# guhPLC_6LowPANModule.net
KiCad netlist of a schematic drawn in EAGLE
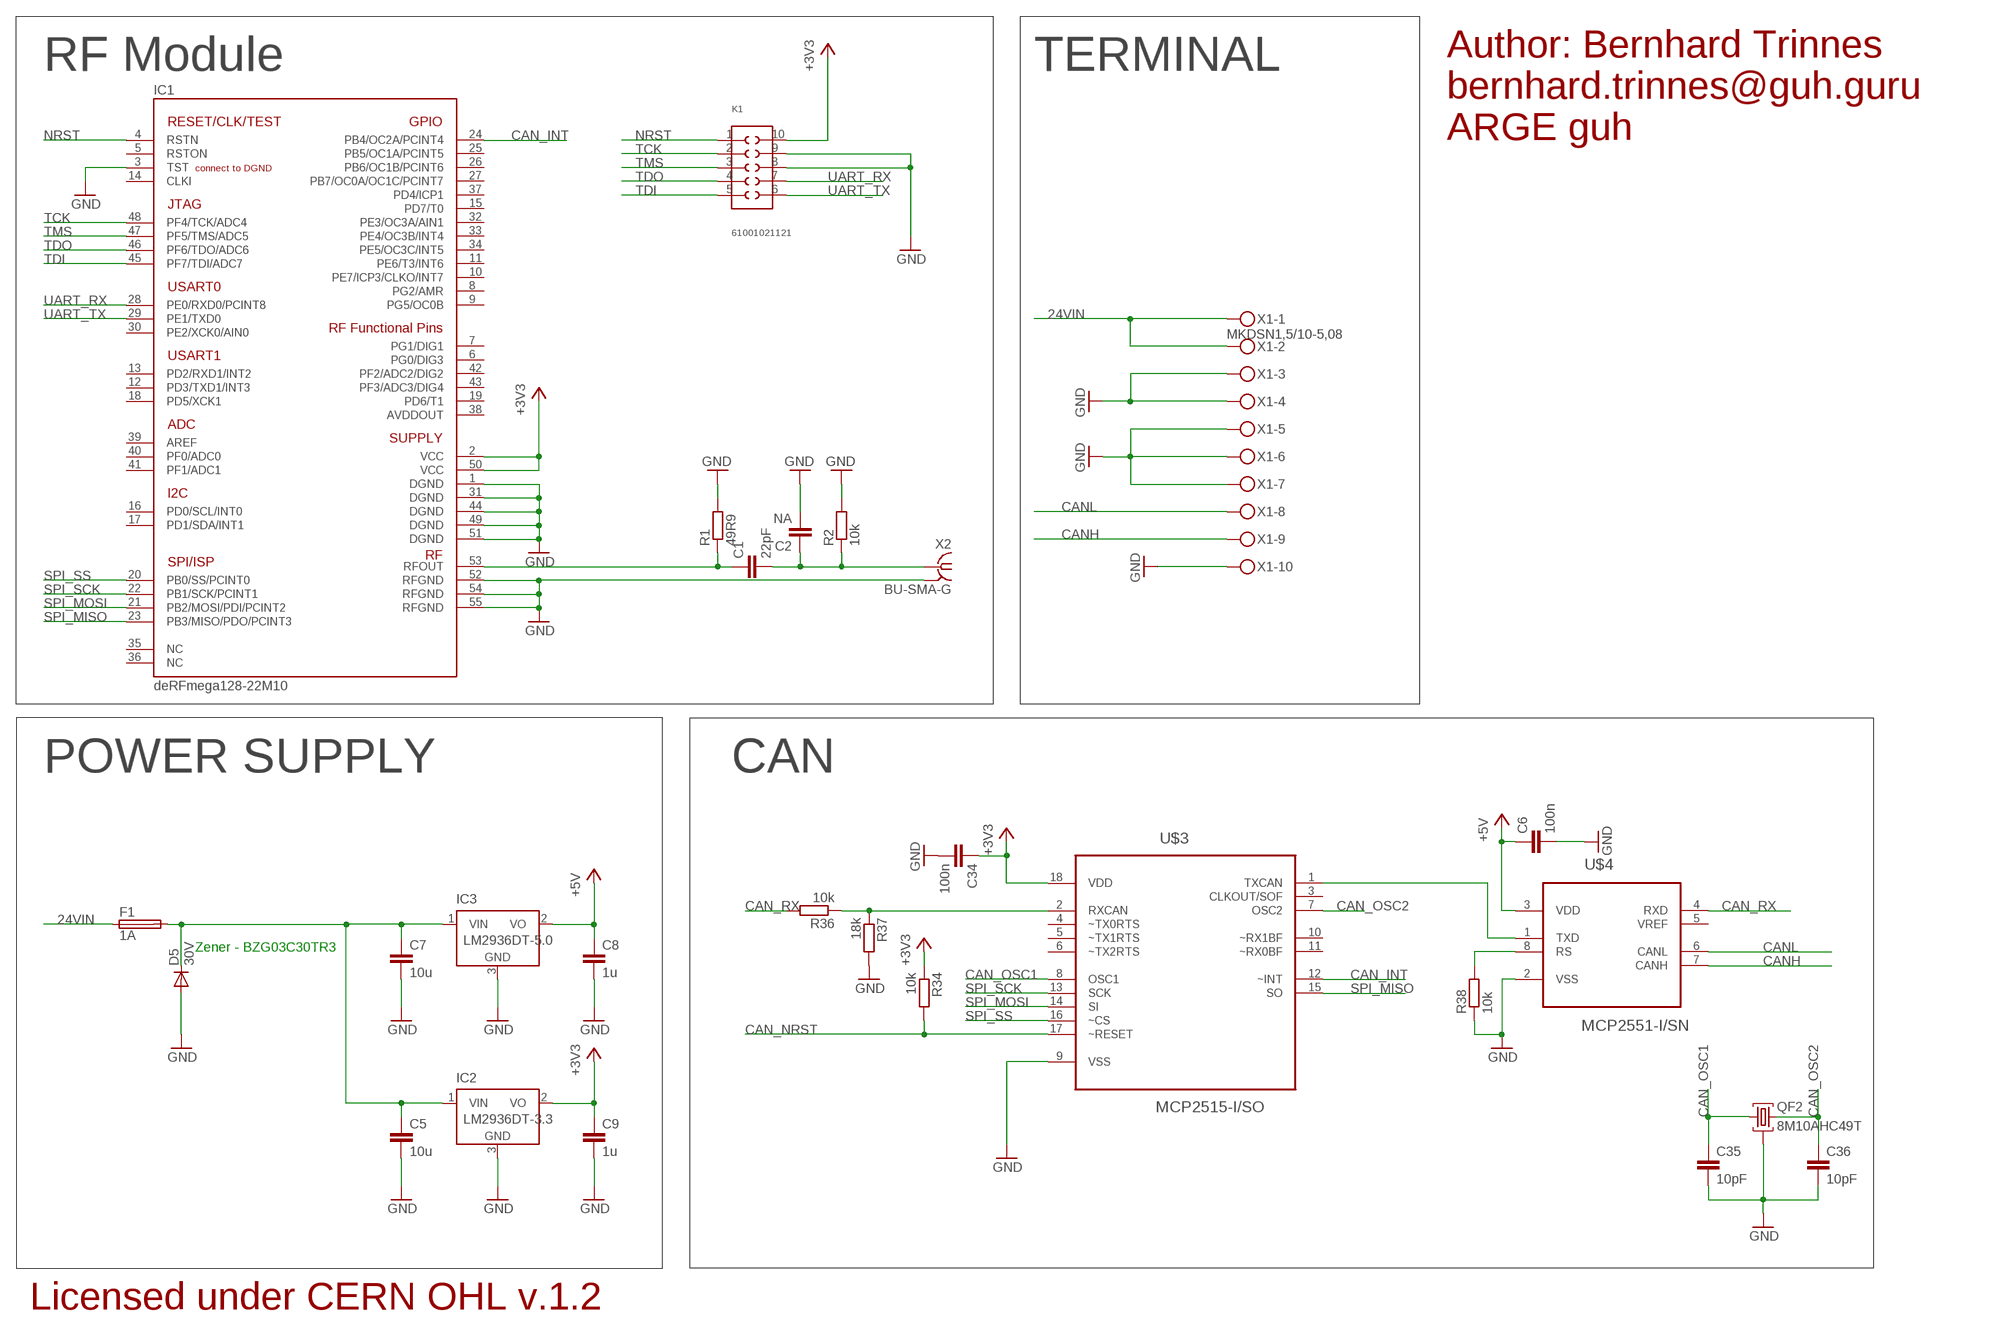
[diagram p0: schematic, sheet 1]

(export (version "E")
  (design (tool "Eeschema 10.0.6"))
  (components
    (comp (ref "C1")
      (value "22pF")
      (footprint "eagle-import:C0402")
      (libsource (lib "eagle-import") (part "C-EUC0402"))
    )
    (comp (ref "C2")
      (value "NA")
      (footprint "eagle-import:C0402")
      (libsource (lib "eagle-import") (part "C-EUC0402"))
    )
    (comp (ref "C5")
      (value "10u")
      (footprint "eagle-import:C1206")
      (libsource (lib "eagle-import") (part "C-EUC1206"))
    )
    (comp (ref "C6")
      (value "100n")
      (footprint "eagle-import:C0603")
      (libsource (lib "eagle-import") (part "C-EUC0603"))
    )
    (comp (ref "C7")
      (value "10u")
      (footprint "eagle-import:C1206")
      (libsource (lib "eagle-import") (part "C-EUC1206"))
    )
    (comp (ref "C8")
      (value "1u")
      (footprint "eagle-import:C0603")
      (libsource (lib "eagle-import") (part "C-EUC0603"))
    )
    (comp (ref "C9")
      (value "1u")
      (footprint "eagle-import:C0603")
      (libsource (lib "eagle-import") (part "C-EUC0603"))
    )
    (comp (ref "C34")
      (value "100n")
      (footprint "eagle-import:C0603")
      (libsource (lib "eagle-import") (part "C-EUC0603"))
    )
    (comp (ref "C35")
      (value "10pF")
      (footprint "eagle-import:C0603")
      (libsource (lib "eagle-import") (part "C-EUC0603"))
    )
    (comp (ref "C36")
      (value "10pF")
      (footprint "eagle-import:C0603")
      (libsource (lib "eagle-import") (part "C-EUC0603"))
    )
    (comp (ref "D5")
      (value "30V")
      (footprint "eagle-import:DO214AC")
      (libsource (lib "eagle-import") (part "DIODE-DO214AC"))
    )
    (comp (ref "F1")
      (value "1A")
      (footprint "eagle-import:LITTLEFUSE")
      (libsource (lib "eagle-import") (part "LITTLEFUSE"))
    )
    (comp (ref "IC1")
      (value "DERFMEGA128-22M10")
      (footprint "eagle-import:A-M10")
      (libsource (lib "eagle-import") (part "DERFMEGA128-22M10"))
    )
    (comp (ref "IC2")
      (value "LM2936DT-3.3")
      (footprint "eagle-import:TO252")
      (fields (field (name "MPN") "LM2936DT-3.3."))
      (libsource (lib "eagle-import") (part "LM2936?DT-3.3"))
    )
    (comp (ref "IC3")
      (value "LM2936DT-5.0")
      (footprint "eagle-import:TO252")
      (fields (field (name "MF") "NATIONAL SEMICONDUCTOR") (field (name "MPN") "LM2936DT-5.0/NOPB"))
      (libsource (lib "eagle-import") (part "LM2936?DT-5.0"))
    )
    (comp (ref "K1")
      (value "61001021121")
      (footprint "eagle-import:61001021121")
      (libsource (lib "eagle-import") (part "61001021121"))
    )
    (comp (ref "QF2")
      (value "8M10AHC49T")
      (footprint "eagle-import:HC49U")
      (fields (field (name "OC_FARNELL") "unknown") (field (name "OC_NEWARK") "unknown"))
      (libsource (lib "eagle-import") (part "8M10AHC49T"))
    )
    (comp (ref "R1")
      (value "49R9")
      (footprint "eagle-import:R0402")
      (libsource (lib "eagle-import") (part "R-EU_R0402"))
    )
    (comp (ref "R2")
      (value "10k")
      (footprint "eagle-import:R0402")
      (libsource (lib "eagle-import") (part "R-EU_R0402"))
    )
    (comp (ref "R34")
      (value "10k")
      (footprint "eagle-import:R0603")
      (libsource (lib "eagle-import") (part "R-EU_R0603"))
    )
    (comp (ref "R36")
      (value "10k")
      (footprint "eagle-import:R0603")
      (libsource (lib "eagle-import") (part "R-EU_R0603"))
    )
    (comp (ref "R37")
      (value "18k")
      (footprint "eagle-import:R0603")
      (libsource (lib "eagle-import") (part "R-EU_R0603"))
    )
    (comp (ref "R38")
      (value "10k")
      (footprint "eagle-import:R0603")
      (libsource (lib "eagle-import") (part "R-EU_R0603"))
    )
    (comp (ref "U$3")
      (value "MCP2515-I/SO")
      (footprint "eagle-import:SOIC127P1034X264-18N")
      (libsource (lib "eagle-import") (part "MCP2515-I/SO"))
    )
    (comp (ref "U$4")
      (value "MCP2551-I/SN")
      (footprint "eagle-import:SOIC127P600X175-8N")
      (libsource (lib "eagle-import") (part "MCP2551-I/SN"))
    )
    (comp (ref "X1")
      (value "MKDSN1,5/10-5,08")
      (footprint "eagle-import:MKDSN1,5_10-5,08")
      (fields (field (name "MPN") "SMKDSN1,5/10-5,08"))
      (libsource (lib "eagle-import") (part "MKDSN1,5/10-5,08"))
    )
    (comp (ref "X2")
      (value "BU-SMA-G")
      (footprint "eagle-import:BU-SMA-G")
      (libsource (lib "eagle-import") (part "BU-SMA-G"))
    )
  )
  (nets
    (net (code "1") (name "+3V3") (class "Default")
      (node (ref "C34") (pin "1") (pinfunction "1_1") (pintype "passive"))
      (node (ref "C9") (pin "1") (pinfunction "1_1") (pintype "passive"))
      (node (ref "IC1") (pin "2") (pinfunction "VCC_2") (pintype "power_in"))
      (node (ref "IC1") (pin "50") (pinfunction "VCC_50") (pintype "power_in"))
      (node (ref "IC2") (pin "2") (pinfunction "VO_2") (pintype "passive"))
      (node (ref "K1") (pin "10") (pinfunction "10_10") (pintype "passive"))
      (node (ref "R34") (pin "1") (pinfunction "1_1") (pintype "passive"))
      (node (ref "U$3") (pin "18") (pinfunction "VDD_18") (pintype "power_in"))
    )
    (net (code "2") (name "+5V") (class "Default")
      (node (ref "C6") (pin "1") (pinfunction "1_1") (pintype "passive"))
      (node (ref "C8") (pin "1") (pinfunction "1_1") (pintype "passive"))
      (node (ref "IC3") (pin "2") (pinfunction "VO_2") (pintype "passive"))
      (node (ref "U$4") (pin "3") (pinfunction "VDD_3") (pintype "power_in"))
    )
    (net (code "3") (name "/24VIN") (class "Default")
      (node (ref "F1") (pin "1") (pinfunction "1_1") (pintype "passive"))
      (node (ref "X1") (pin "1") (pinfunction "KL_1") (pintype "passive"))
      (node (ref "X1") (pin "2") (pinfunction "KL_2") (pintype "passive"))
    )
    (net (code "4") (name "/CANH") (class "Default")
      (node (ref "U$4") (pin "7") (pinfunction "CANH_7") (pintype "bidirectional"))
      (node (ref "X1") (pin "9") (pinfunction "KL_9") (pintype "passive"))
    )
    (net (code "5") (name "/CANL") (class "Default")
      (node (ref "U$4") (pin "6") (pinfunction "CANL_6") (pintype "bidirectional"))
      (node (ref "X1") (pin "8") (pinfunction "KL_8") (pintype "passive"))
    )
    (net (code "6") (name "/CAN_INT") (class "Default")
      (node (ref "IC1") (pin "24") (pinfunction "PB4/OC2A/PCINT4_24") (pintype "bidirectional"))
      (node (ref "U$3") (pin "12") (pinfunction "~{INT}_12") (pintype "output"))
    )
    (net (code "7") (name "/CAN_NRST") (class "Default")
      (node (ref "R34") (pin "2") (pinfunction "2_2") (pintype "passive"))
      (node (ref "U$3") (pin "17") (pinfunction "~{RESET}_17") (pintype "input"))
    )
    (net (code "8") (name "/CAN_OSC1") (class "Default")
      (node (ref "C35") (pin "1") (pinfunction "1_1") (pintype "passive"))
      (node (ref "QF2") (pin "1") (pinfunction "1_1") (pintype "passive"))
      (node (ref "U$3") (pin "8") (pinfunction "OSC1_8") (pintype "input"))
    )
    (net (code "9") (name "/CAN_OSC2") (class "Default")
      (node (ref "C36") (pin "1") (pinfunction "1_1") (pintype "passive"))
      (node (ref "QF2") (pin "3") (pinfunction "3_3") (pintype "passive"))
      (node (ref "U$3") (pin "7") (pinfunction "OSC2_7") (pintype "output"))
    )
    (net (code "10") (name "/CAN_RX") (class "Default")
      (node (ref "R36") (pin "2") (pinfunction "2_2") (pintype "passive"))
      (node (ref "U$4") (pin "4") (pinfunction "RXD_4") (pintype "output"))
    )
    (net (code "11") (name "/NRST") (class "Default")
      (node (ref "IC1") (pin "4") (pinfunction "RSTN_4") (pintype "input"))
      (node (ref "K1") (pin "1") (pinfunction "1_1") (pintype "passive"))
    )
    (net (code "12") (name "/SPI_MISO") (class "Default")
      (node (ref "IC1") (pin "23") (pinfunction "PB3/MISO/PDO/PCINT3_23") (pintype "bidirectional"))
      (node (ref "U$3") (pin "15") (pinfunction "SO_15") (pintype "output"))
    )
    (net (code "13") (name "/SPI_MOSI") (class "Default")
      (node (ref "IC1") (pin "21") (pinfunction "PB2/MOSI/PDI/PCINT2_21") (pintype "bidirectional"))
      (node (ref "U$3") (pin "14") (pinfunction "SI_14") (pintype "input"))
    )
    (net (code "14") (name "/SPI_SCK") (class "Default")
      (node (ref "IC1") (pin "22") (pinfunction "PB1/SCK/PCINT1_22") (pintype "bidirectional"))
      (node (ref "U$3") (pin "13") (pinfunction "SCK_13") (pintype "input"))
    )
    (net (code "15") (name "/SPI_SS") (class "Default")
      (node (ref "IC1") (pin "20") (pinfunction "PB0/SS/PCINT0_20") (pintype "bidirectional"))
      (node (ref "U$3") (pin "16") (pinfunction "~{CS}_16") (pintype "input"))
    )
    (net (code "16") (name "/TCK") (class "Default")
      (node (ref "IC1") (pin "48") (pinfunction "PF4/TCK/ADC4_48") (pintype "bidirectional"))
      (node (ref "K1") (pin "2") (pinfunction "2_2") (pintype "passive"))
    )
    (net (code "17") (name "/TDI") (class "Default")
      (node (ref "IC1") (pin "45") (pinfunction "PF7/TDI/ADC7_45") (pintype "bidirectional"))
      (node (ref "K1") (pin "5") (pinfunction "5_5") (pintype "passive"))
    )
    (net (code "18") (name "/TDO") (class "Default")
      (node (ref "IC1") (pin "46") (pinfunction "PF6/TDO/ADC6_46") (pintype "bidirectional"))
      (node (ref "K1") (pin "4") (pinfunction "4_4") (pintype "passive"))
    )
    (net (code "19") (name "/TMS") (class "Default")
      (node (ref "IC1") (pin "47") (pinfunction "PF5/TMS/ADC5_47") (pintype "bidirectional"))
      (node (ref "K1") (pin "3") (pinfunction "3_3") (pintype "passive"))
    )
    (net (code "20") (name "/UART_RX") (class "Default")
      (node (ref "IC1") (pin "28") (pinfunction "PE0/RXD0/PCINT8_28") (pintype "bidirectional"))
      (node (ref "K1") (pin "7") (pinfunction "7_7") (pintype "passive"))
    )
    (net (code "21") (name "/UART_TX") (class "Default")
      (node (ref "IC1") (pin "29") (pinfunction "PE1/TXD0_29") (pintype "bidirectional"))
      (node (ref "K1") (pin "6") (pinfunction "6_6") (pintype "passive"))
    )
    (net (code "22") (name "GND") (class "Default")
      (node (ref "C2") (pin "2") (pinfunction "2_2") (pintype "passive"))
      (node (ref "C34") (pin "2") (pinfunction "2_2") (pintype "passive"))
      (node (ref "C35") (pin "2") (pinfunction "2_2") (pintype "passive"))
      (node (ref "C36") (pin "2") (pinfunction "2_2") (pintype "passive"))
      (node (ref "C5") (pin "2") (pinfunction "2_2") (pintype "passive"))
      (node (ref "C6") (pin "2") (pinfunction "2_2") (pintype "passive"))
      (node (ref "C7") (pin "2") (pinfunction "2_2") (pintype "passive"))
      (node (ref "C8") (pin "2") (pinfunction "2_2") (pintype "passive"))
      (node (ref "C9") (pin "2") (pinfunction "2_2") (pintype "passive"))
      (node (ref "D5") (pin "A") (pinfunction "A_A") (pintype "passive"))
      (node (ref "IC1") (pin "1") (pinfunction "DGND_1") (pintype "power_in"))
      (node (ref "IC1") (pin "3") (pinfunction "TST_3") (pintype "input"))
      (node (ref "IC1") (pin "31") (pinfunction "DGND_31") (pintype "power_in"))
      (node (ref "IC1") (pin "44") (pinfunction "DGND_44") (pintype "power_in"))
      (node (ref "IC1") (pin "49") (pinfunction "DGND_49") (pintype "power_in"))
      (node (ref "IC1") (pin "51") (pinfunction "DGND_51") (pintype "power_in"))
      (node (ref "IC1") (pin "52") (pinfunction "RFGND_52") (pintype "power_in"))
      (node (ref "IC1") (pin "54") (pinfunction "RFGND_54") (pintype "power_in"))
      (node (ref "IC1") (pin "55") (pinfunction "RFGND_55") (pintype "power_in"))
      (node (ref "IC2") (pin "3") (pinfunction "GND_3") (pintype "passive"))
      (node (ref "IC3") (pin "3") (pinfunction "GND_3") (pintype "passive"))
      (node (ref "K1") (pin "8") (pinfunction "8_8") (pintype "passive"))
      (node (ref "K1") (pin "9") (pinfunction "9_9") (pintype "passive"))
      (node (ref "QF2") (pin "2") (pinfunction "2_2") (pintype "passive"))
      (node (ref "R1") (pin "2") (pinfunction "2_2") (pintype "passive"))
      (node (ref "R2") (pin "2") (pinfunction "2_2") (pintype "passive"))
      (node (ref "R37") (pin "2") (pinfunction "2_2") (pintype "passive"))
      (node (ref "R38") (pin "1") (pinfunction "1_1") (pintype "passive"))
      (node (ref "U$3") (pin "9") (pinfunction "VSS_9") (pintype "power_in"))
      (node (ref "U$4") (pin "2") (pinfunction "VSS_2") (pintype "passive"))
      (node (ref "X1") (pin "10") (pinfunction "KL_10") (pintype "passive"))
      (node (ref "X1") (pin "3") (pinfunction "KL_3") (pintype "passive"))
      (node (ref "X1") (pin "4") (pinfunction "KL_4") (pintype "passive"))
      (node (ref "X1") (pin "5") (pinfunction "KL_5") (pintype "passive"))
      (node (ref "X1") (pin "6") (pinfunction "KL_6") (pintype "passive"))
      (node (ref "X1") (pin "7") (pinfunction "KL_7") (pintype "passive"))
      (node (ref "X2") (pin "2") (pinfunction "GND_2") (pintype "power_in"))
    )
    (net (code "23") (name "Net-(C1-Pad2)") (class "Default")
      (node (ref "C1") (pin "2") (pinfunction "2_2") (pintype "passive"))
      (node (ref "C2") (pin "1") (pinfunction "1_1") (pintype "passive"))
      (node (ref "R2") (pin "1") (pinfunction "1_1") (pintype "passive"))
      (node (ref "X2") (pin "1") (pinfunction "1_1") (pintype "passive"))
    )
    (net (code "24") (name "Net-(IC1-RFOUT)") (class "Default")
      (node (ref "C1") (pin "1") (pinfunction "1_1") (pintype "passive"))
      (node (ref "IC1") (pin "53") (pinfunction "RFOUT_53") (pintype "power_in"))
      (node (ref "R1") (pin "1") (pinfunction "1_1") (pintype "passive"))
    )
    (net (code "25") (name "Net-(IC2-VIN)") (class "Default")
      (node (ref "C5") (pin "1") (pinfunction "1_1") (pintype "passive"))
      (node (ref "C7") (pin "1") (pinfunction "1_1") (pintype "passive"))
      (node (ref "D5") (pin "C") (pinfunction "C_C") (pintype "passive"))
      (node (ref "F1") (pin "2") (pinfunction "2_2") (pintype "passive"))
      (node (ref "IC2") (pin "1") (pinfunction "VIN_1") (pintype "input"))
      (node (ref "IC3") (pin "1") (pinfunction "VIN_1") (pintype "input"))
    )
    (net (code "26") (name "Net-(U$3-RXCAN)") (class "Default")
      (node (ref "R36") (pin "1") (pinfunction "1_1") (pintype "passive"))
      (node (ref "R37") (pin "1") (pinfunction "1_1") (pintype "passive"))
      (node (ref "U$3") (pin "2") (pinfunction "RXCAN_2") (pintype "input"))
    )
    (net (code "27") (name "Net-(U$3-TXCAN)") (class "Default")
      (node (ref "U$3") (pin "1") (pinfunction "TXCAN_1") (pintype "output"))
      (node (ref "U$4") (pin "1") (pinfunction "TXD_1") (pintype "input"))
    )
    (net (code "28") (name "Net-(U$4-RS)") (class "Default")
      (node (ref "R38") (pin "2") (pinfunction "2_2") (pintype "passive"))
      (node (ref "U$4") (pin "8") (pinfunction "RS_8") (pintype "input"))
    )
    (net (code "29") (name "unconnected-(IC1-AREF-Pad39)") (class "Default")
      (node (ref "IC1") (pin "39") (pinfunction "AREF_39") (pintype "bidirectional"))
    )
    (net (code "30") (name "unconnected-(IC1-AVDDOUT-Pad38)") (class "Default")
      (node (ref "IC1") (pin "38") (pinfunction "AVDDOUT_38") (pintype "output"))
    )
    (net (code "31") (name "unconnected-(IC1-CLKI-Pad14)") (class "Default")
      (node (ref "IC1") (pin "14") (pinfunction "CLKI_14") (pintype "input"))
    )
    (net (code "32") (name "unconnected-(IC1-NC-Pad35)") (class "Default")
      (node (ref "IC1") (pin "35") (pinfunction "NC_35") (pintype "no_connect"))
    )
    (net (code "33") (name "unconnected-(IC1-NC-Pad36)") (class "Default")
      (node (ref "IC1") (pin "36") (pinfunction "NC_36") (pintype "no_connect"))
    )
    (net (code "34") (name "unconnected-(IC1-PB5{slash}OC1A{slash}PCINT5-Pad25)") (class "Default")
      (node (ref "IC1") (pin "25") (pinfunction "PB5/OC1A/PCINT5_25") (pintype "bidirectional"))
    )
    (net (code "35") (name "unconnected-(IC1-PB6{slash}OC1B{slash}PCINT6-Pad26)") (class "Default")
      (node (ref "IC1") (pin "26") (pinfunction "PB6/OC1B/PCINT6_26") (pintype "bidirectional"))
    )
    (net (code "36") (name "unconnected-(IC1-PB7{slash}OC0A{slash}OC1C{slash}PCINT7-Pad27)") (class "Default")
      (node (ref "IC1") (pin "27") (pinfunction "PB7/OC0A/OC1C/PCINT7_27") (pintype "bidirectional"))
    )
    (net (code "37") (name "unconnected-(IC1-PD0{slash}SCL{slash}INT0-Pad16)") (class "Default")
      (node (ref "IC1") (pin "16") (pinfunction "PD0/SCL/INT0_16") (pintype "bidirectional"))
    )
    (net (code "38") (name "unconnected-(IC1-PD1{slash}SDA{slash}INT1-Pad17)") (class "Default")
      (node (ref "IC1") (pin "17") (pinfunction "PD1/SDA/INT1_17") (pintype "bidirectional"))
    )
    (net (code "39") (name "unconnected-(IC1-PD2{slash}RXD1{slash}INT2-Pad13)") (class "Default")
      (node (ref "IC1") (pin "13") (pinfunction "PD2/RXD1/INT2_13") (pintype "bidirectional"))
    )
    (net (code "40") (name "unconnected-(IC1-PD3{slash}TXD1{slash}INT3-Pad12)") (class "Default")
      (node (ref "IC1") (pin "12") (pinfunction "PD3/TXD1/INT3_12") (pintype "bidirectional"))
    )
    (net (code "41") (name "unconnected-(IC1-PD4{slash}ICP1-Pad37)") (class "Default")
      (node (ref "IC1") (pin "37") (pinfunction "PD4/ICP1_37") (pintype "bidirectional"))
    )
    (net (code "42") (name "unconnected-(IC1-PD5{slash}XCK1-Pad18)") (class "Default")
      (node (ref "IC1") (pin "18") (pinfunction "PD5/XCK1_18") (pintype "bidirectional"))
    )
    (net (code "43") (name "unconnected-(IC1-PD6{slash}T1-Pad19)") (class "Default")
      (node (ref "IC1") (pin "19") (pinfunction "PD6/T1_19") (pintype "bidirectional"))
    )
    (net (code "44") (name "unconnected-(IC1-PD7{slash}T0-Pad15)") (class "Default")
      (node (ref "IC1") (pin "15") (pinfunction "PD7/T0_15") (pintype "bidirectional"))
    )
    (net (code "45") (name "unconnected-(IC1-PE2{slash}XCK0{slash}AIN0-Pad30)") (class "Default")
      (node (ref "IC1") (pin "30") (pinfunction "PE2/XCK0/AIN0_30") (pintype "bidirectional"))
    )
    (net (code "46") (name "unconnected-(IC1-PE3{slash}OC3A{slash}AIN1-Pad32)") (class "Default")
      (node (ref "IC1") (pin "32") (pinfunction "PE3/OC3A/AIN1_32") (pintype "bidirectional"))
    )
    (net (code "47") (name "unconnected-(IC1-PE4{slash}OC3B{slash}INT4-Pad33)") (class "Default")
      (node (ref "IC1") (pin "33") (pinfunction "PE4/OC3B/INT4_33") (pintype "bidirectional"))
    )
    (net (code "48") (name "unconnected-(IC1-PE5{slash}OC3C{slash}INT5-Pad34)") (class "Default")
      (node (ref "IC1") (pin "34") (pinfunction "PE5/OC3C/INT5_34") (pintype "bidirectional"))
    )
    (net (code "49") (name "unconnected-(IC1-PE6{slash}T3{slash}INT6-Pad11)") (class "Default")
      (node (ref "IC1") (pin "11") (pinfunction "PE6/T3/INT6_11") (pintype "bidirectional"))
    )
    (net (code "50") (name "unconnected-(IC1-PE7{slash}ICP3{slash}CLKO{slash}INT7-Pad10)") (class "Default")
      (node (ref "IC1") (pin "10") (pinfunction "PE7/ICP3/CLKO/INT7_10") (pintype "bidirectional"))
    )
    (net (code "51") (name "unconnected-(IC1-PF0{slash}ADC0-Pad40)") (class "Default")
      (node (ref "IC1") (pin "40") (pinfunction "PF0/ADC0_40") (pintype "bidirectional"))
    )
    (net (code "52") (name "unconnected-(IC1-PF1{slash}ADC1-Pad41)") (class "Default")
      (node (ref "IC1") (pin "41") (pinfunction "PF1/ADC1_41") (pintype "bidirectional"))
    )
    (net (code "53") (name "unconnected-(IC1-PF2{slash}ADC2{slash}DIG2-Pad42)") (class "Default")
      (node (ref "IC1") (pin "42") (pinfunction "PF2/ADC2/DIG2_42") (pintype "bidirectional"))
    )
    (net (code "54") (name "unconnected-(IC1-PF3{slash}ADC3{slash}DIG4-Pad43)") (class "Default")
      (node (ref "IC1") (pin "43") (pinfunction "PF3/ADC3/DIG4_43") (pintype "bidirectional"))
    )
    (net (code "55") (name "unconnected-(IC1-PG0{slash}DIG3-Pad6)") (class "Default")
      (node (ref "IC1") (pin "6") (pinfunction "PG0/DIG3_6") (pintype "bidirectional"))
    )
    (net (code "56") (name "unconnected-(IC1-PG1{slash}DIG1-Pad7)") (class "Default")
      (node (ref "IC1") (pin "7") (pinfunction "PG1/DIG1_7") (pintype "bidirectional"))
    )
    (net (code "57") (name "unconnected-(IC1-PG2{slash}AMR-Pad8)") (class "Default")
      (node (ref "IC1") (pin "8") (pinfunction "PG2/AMR_8") (pintype "bidirectional"))
    )
    (net (code "58") (name "unconnected-(IC1-PG5{slash}OC0B-Pad9)") (class "Default")
      (node (ref "IC1") (pin "9") (pinfunction "PG5/OC0B_9") (pintype "bidirectional"))
    )
    (net (code "59") (name "unconnected-(IC1-RSTON-Pad5)") (class "Default")
      (node (ref "IC1") (pin "5") (pinfunction "RSTON_5") (pintype "output"))
    )
    (net (code "60") (name "unconnected-(U$3-CLKOUT{slash}SOF-Pad3)") (class "Default")
      (node (ref "U$3") (pin "3") (pinfunction "CLKOUT/SOF_3") (pintype "output"))
    )
    (net (code "61") (name "unconnected-(U$3-~{RX0BF}-Pad11)") (class "Default")
      (node (ref "U$3") (pin "11") (pinfunction "~{RX0BF}_11") (pintype "output"))
    )
    (net (code "62") (name "unconnected-(U$3-~{RX1BF}-Pad10)") (class "Default")
      (node (ref "U$3") (pin "10") (pinfunction "~{RX1BF}_10") (pintype "output"))
    )
    (net (code "63") (name "unconnected-(U$3-~{TX0RTS}-Pad4)") (class "Default")
      (node (ref "U$3") (pin "4") (pinfunction "~{TX0RTS}_4") (pintype "input"))
    )
    (net (code "64") (name "unconnected-(U$3-~{TX1RTS}-Pad5)") (class "Default")
      (node (ref "U$3") (pin "5") (pinfunction "~{TX1RTS}_5") (pintype "input"))
    )
    (net (code "65") (name "unconnected-(U$3-~{TX2RTS}-Pad6)") (class "Default")
      (node (ref "U$3") (pin "6") (pinfunction "~{TX2RTS}_6") (pintype "input"))
    )
    (net (code "66") (name "unconnected-(U$4-VREF-Pad5)") (class "Default")
      (node (ref "U$4") (pin "5") (pinfunction "VREF_5") (pintype "output"))
    )
  )
)
